# microcontroller.net
KiCad netlist of a schematic drawn in Altium Designer
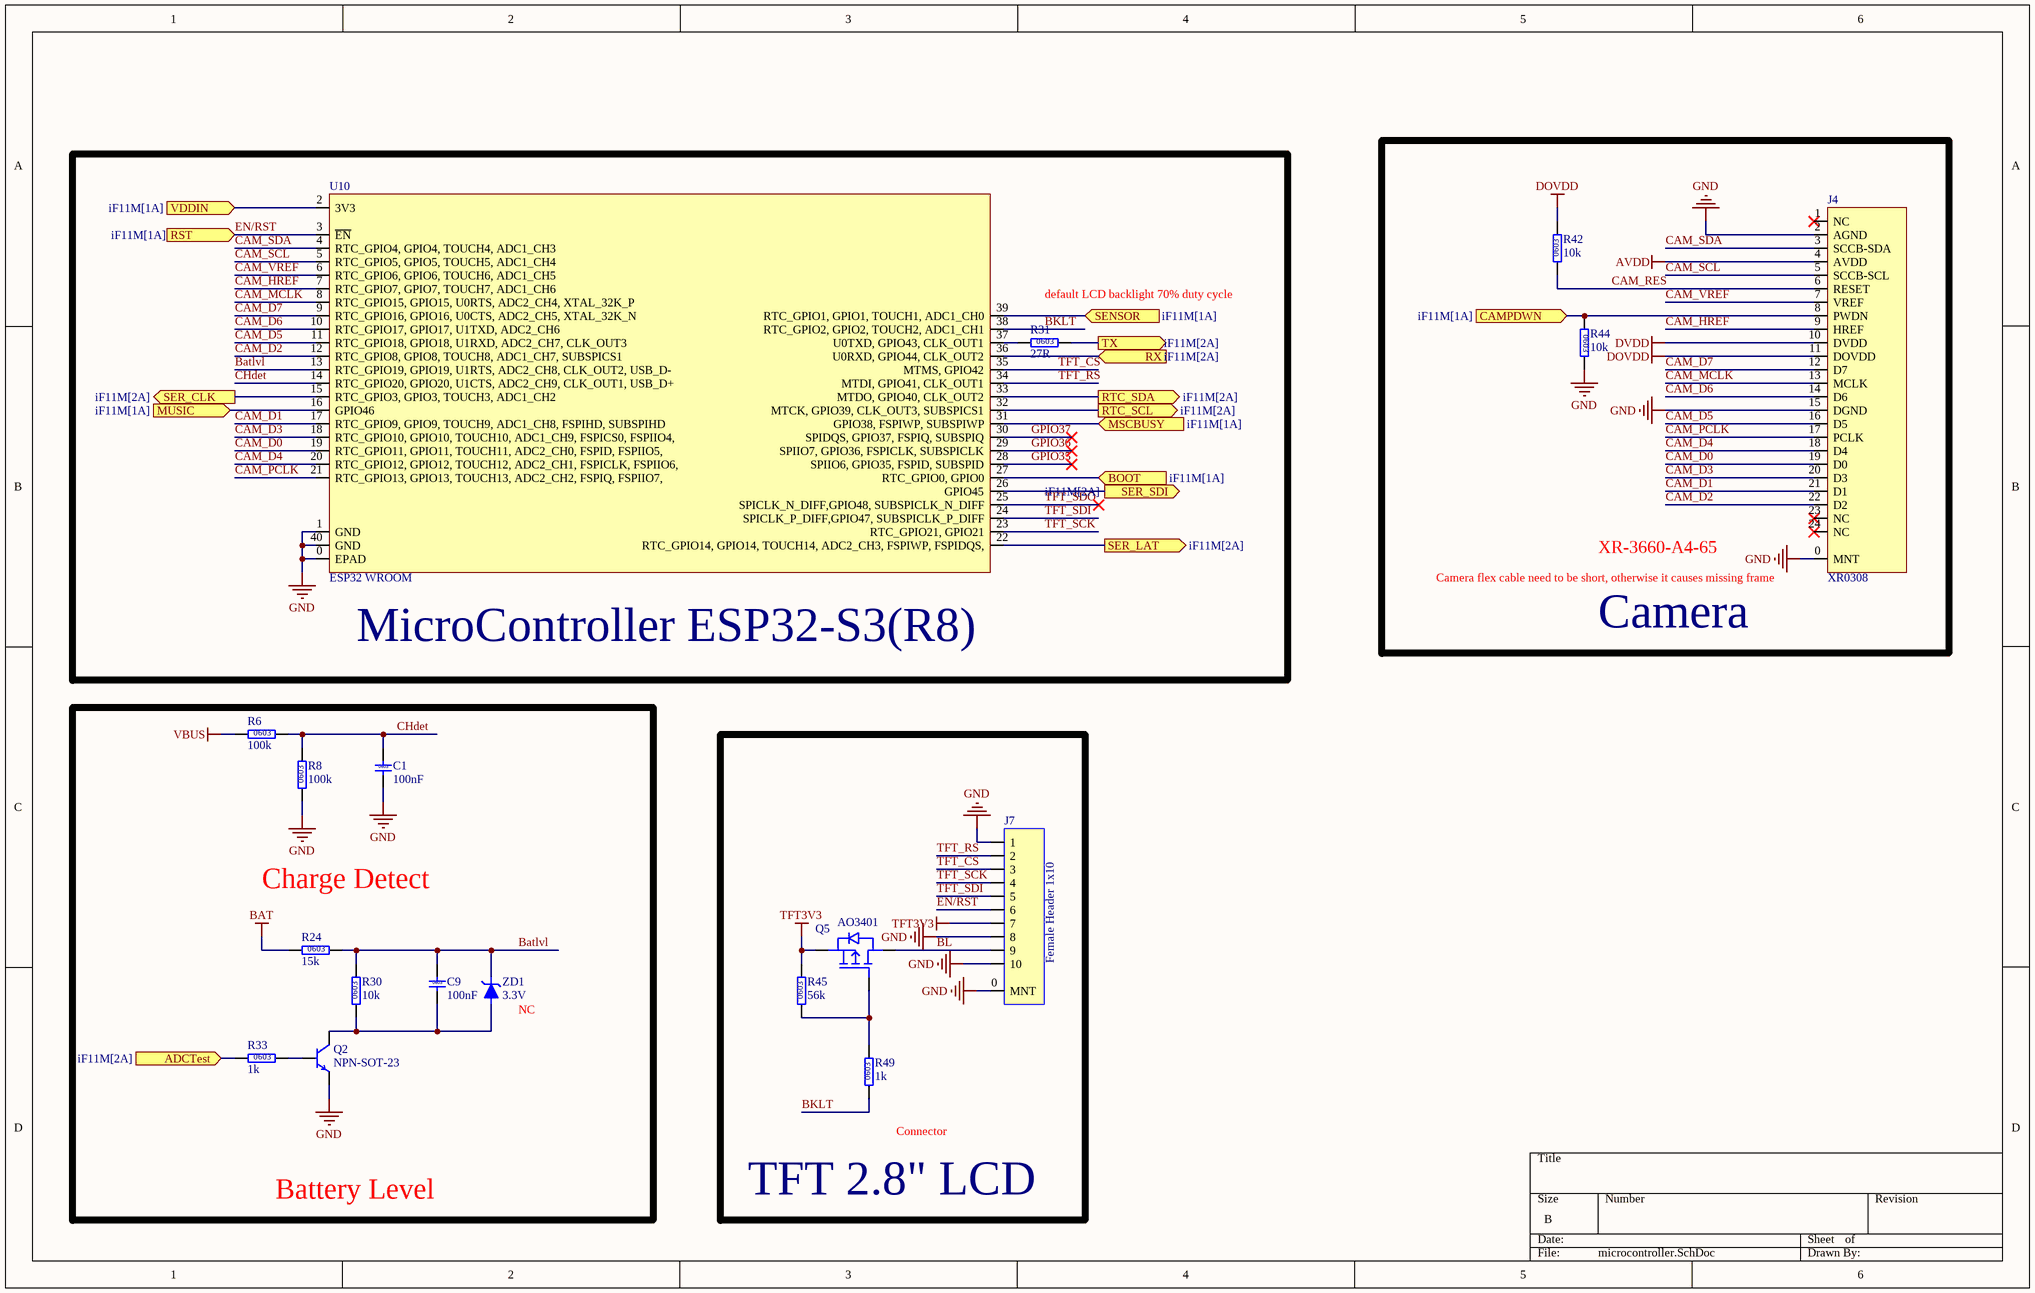
[diagram p0: microcontroller.SchDoc]

(export (version "E")
  (design (tool "Eeschema 10.0.6"))
  (components
    (comp (ref "C1")
      (value "100nF")
      (footprint "C0603")
      (description "10% 50V")
      (fields (field (name "PART NO") "W-T-CA-X703N100K50VNT") (field (name "MANUFACTURER") "FENGHUA"))
      (libsource (lib "Rescap") (part "C 0603 100nF 50V"))
    )
    (comp (ref "C9")
      (value "100nF")
      (footprint "C0603")
      (description "10% 50V")
      (fields (field (name "PART NO") "W-T-CA-X703N100K50VNT") (field (name "MANUFACTURER") "FENGHUA"))
      (libsource (lib "Rescap") (part "C 0603 100nF 50V"))
    )
    (comp (ref "J4")
      (value "XR0308")
      (footprint "FPC24-0.5P-TOP")
      (libsource (lib "Connector") (part "XR0308-TOP"))
    )
    (comp (ref "J7")
      (value "Female Header 1x10")
      (footprint "FPC10-1mm-SMT  BOTTOM")
      (description "10 Pin FPC BOTTOM Contact")
      (libsource (lib "Connector") (part "FPC10P-1mm-BOT"))
    )
    (comp (ref "Q2")
      (value "NPN-SOT-23")
      (footprint "SOT23")
      (libsource (lib "Transistor") (part "NPN-SOT-23"))
    )
    (comp (ref "Q5")
      (value "AO3401")
      (footprint "PMOS-SOT23")
      (description "MOSFET-P-Channel")
      (libsource (lib "Transistor") (part "MOSFET-P-Channel"))
    )
    (comp (ref "R6")
      (value "100k")
      (footprint "R0603-LD")
      (description "5%")
      (fields (field (name "PART NO") "W-T-RE-RS03K104JT") (field (name "MANUFACTURER") "LAGEO"))
      (libsource (lib "Rescap") (part "R 0603 100k"))
    )
    (comp (ref "R8")
      (value "100k")
      (footprint "R0603-LD")
      (description "5%")
      (fields (field (name "PART NO") "W-T-RE-RS03K104JT") (field (name "MANUFACTURER") "LAGEO"))
      (libsource (lib "Rescap") (part "R 0603 100k"))
    )
    (comp (ref "R24")
      (value "15k")
      (footprint "R0603-LD")
      (description "5%")
      (fields (field (name "PART NO") "W-T-RE-RS03K104JT") (field (name "MANUFACTURER") "LAGEO"))
      (libsource (lib "Rescap") (part "R 0603 100k"))
    )
    (comp (ref "R30")
      (value "10k")
      (footprint "R0603-LD")
      (description "5%")
      (fields (field (name "PART NO") "W-T-RE-RS03K104JT") (field (name "MANUFACTURER") "LAGEO"))
      (libsource (lib "Rescap") (part "R 0603 100k"))
    )
    (comp (ref "R31")
      (value "27R")
      (footprint "R0603-LD")
      (description "5%")
      (fields (field (name "PART NO") "W-T-RE-RS03K270JT") (field (name "MANUFACTURER") "LAGEO"))
      (libsource (lib "Rescap") (part "R 0603 27R"))
    )
    (comp (ref "R33")
      (value "1k")
      (footprint "R0603-LD")
      (description "5%")
      (fields (field (name "PART NO") "W-T-RE-RS03K102JT") (field (name "MANUFACTURER") "LAGEO"))
      (libsource (lib "Rescap") (part "R 0603 1k"))
    )
    (comp (ref "R42")
      (value "10k")
      (footprint "R0603-LD")
      (description "5%")
      (fields (field (name "PART NO") "W-T-RE-RS03K103JT") (field (name "MANUFACTURER") "热敏D541V11增加1颗用量"))
      (libsource (lib "Rescap") (part "R 0603 10k"))
    )
    (comp (ref "R44")
      (value "10k")
      (footprint "R0603-LD")
      (description "5%")
      (fields (field (name "PART NO") "W-T-RE-RS03K103JT") (field (name "MANUFACTURER") "热敏D541V11增加1颗用量"))
      (libsource (lib "Rescap") (part "R 0603 10k"))
    )
    (comp (ref "R45")
      (value "56k")
      (footprint "R0603-LD")
      (description "5%")
      (fields (field (name "PART NO") "W-T-RE-RS03K563JT") (field (name "MANUFACTURER") "LAGEO"))
      (libsource (lib "Rescap") (part "R 0603 56k"))
    )
    (comp (ref "R49")
      (value "1k")
      (footprint "R0603-LD")
      (description "5%")
      (fields (field (name "PART NO") "W-T-RE-RS03K102JT") (field (name "MANUFACTURER") "LAGEO"))
      (libsource (lib "Rescap") (part "R 0603 1k"))
    )
    (comp (ref "U10")
      (value "ESP32 WROOM")
      (footprint "ESP32-S3-WROOM-1")
      (libsource (lib "ICs") (part "ESP32-S3-WROOM-1"))
    )
    (comp (ref "ZD1")
      (value "3.3V")
      (footprint "SOD-323")
      (description "Zener Diode 300mW")
      (libsource (lib "Rectifier") (part "Zener Diode"))
    )
  )
  (nets
    (net (code "1") (name "/ADCTest") (class "Default")
      (node (ref "R33") (pin "1") (pinfunction "1_1") (pintype "passive"))
    )
    (net (code "2") (name "/BKLT") (class "Default")
      (node (ref "R49") (pin "1") (pinfunction "1_1") (pintype "passive"))
      (node (ref "U10") (pin "38") (pinfunction "RTC_GPIO2,_GPIO2,_TOUCH2,_ADC1_CH1_38") (pintype "passive"))
    )
    (net (code "3") (name "/BL") (class "Default")
      (node (ref "J7") (pin "9") (pinfunction "9_9") (pintype "passive"))
      (node (ref "Q5") (pin "2") (pinfunction "D_2") (pintype "passive"))
    )
    (net (code "4") (name "/BOOT") (class "Default")
      (node (ref "U10") (pin "27") (pinfunction "RTC_GPIO0,_GPIO0_27") (pintype "passive"))
    )
    (net (code "5") (name "/Batlvl") (class "Default")
      (node (ref "C9") (pin "1") (pinfunction "1_1") (pintype "passive"))
      (node (ref "R24") (pin "2") (pinfunction "2_2") (pintype "passive"))
      (node (ref "R30") (pin "2") (pinfunction "2_2") (pintype "passive"))
      (node (ref "U10") (pin "13") (pinfunction "RTC_GPIO19,_GPIO19,_U1RTS,_ADC2_CH8,_CLK_OUT2,_USB_D-_13") (pintype "passive"))
      (node (ref "ZD1") (pin "2") (pinfunction "K_2") (pintype "passive"))
    )
    (net (code "6") (name "/CAMPDWN") (class "Default")
      (node (ref "J4") (pin "8") (pinfunction "PWDN_8") (pintype "passive"))
      (node (ref "R44") (pin "1") (pinfunction "1_1") (pintype "passive"))
    )
    (net (code "7") (name "/CAM_D0") (class "Default")
      (node (ref "J4") (pin "19") (pinfunction "D0_19") (pintype "passive"))
      (node (ref "U10") (pin "19") (pinfunction "RTC_GPIO11,_GPIO11,_TOUCH11,_ADC2_CH0,_FSPID,_FSPIIO5,_19") (pintype "passive"))
    )
    (net (code "8") (name "/CAM_D1") (class "Default")
      (node (ref "J4") (pin "21") (pinfunction "D1_21") (pintype "passive"))
      (node (ref "U10") (pin "17") (pinfunction "RTC_GPIO9,_GPIO9,_TOUCH9,_ADC1_CH8,_FSPIHD,_SUBSPIHD_17") (pintype "passive"))
    )
    (net (code "9") (name "/CAM_D2") (class "Default")
      (node (ref "J4") (pin "22") (pinfunction "D2_22") (pintype "passive"))
      (node (ref "U10") (pin "12") (pinfunction "RTC_GPIO8,_GPIO8,_TOUCH8,_ADC1_CH7,_SUBSPICS1_12") (pintype "passive"))
    )
    (net (code "10") (name "/CAM_D3") (class "Default")
      (node (ref "J4") (pin "20") (pinfunction "D3_20") (pintype "passive"))
      (node (ref "U10") (pin "18") (pinfunction "RTC_GPIO10,_GPIO10,_TOUCH10,_ADC1_CH9,_FSPICS0,_FSPIIO4,_18") (pintype "passive"))
    )
    (net (code "11") (name "/CAM_D4") (class "Default")
      (node (ref "J4") (pin "18") (pinfunction "D4_18") (pintype "passive"))
      (node (ref "U10") (pin "20") (pinfunction "RTC_GPIO12,_GPIO12,_TOUCH12,_ADC2_CH1,_FSPICLK,_FSPIIO6,_20") (pintype "passive"))
    )
    (net (code "12") (name "/CAM_D5") (class "Default")
      (node (ref "J4") (pin "16") (pinfunction "D5_16") (pintype "passive"))
      (node (ref "U10") (pin "11") (pinfunction "RTC_GPIO18,_GPIO18,_U1RXD,_ADC2_CH7,_CLK_OUT3_11") (pintype "passive"))
    )
    (net (code "13") (name "/CAM_D6") (class "Default")
      (node (ref "J4") (pin "14") (pinfunction "D6_14") (pintype "passive"))
      (node (ref "U10") (pin "10") (pinfunction "RTC_GPIO17,_GPIO17,_U1TXD,_ADC2_CH6_10") (pintype "passive"))
    )
    (net (code "14") (name "/CAM_D7") (class "Default")
      (node (ref "J4") (pin "12") (pinfunction "D7_12") (pintype "passive"))
      (node (ref "U10") (pin "9") (pinfunction "RTC_GPIO16,_GPIO16,_U0CTS,_ADC2_CH5,_XTAL_32K_N_9") (pintype "passive"))
    )
    (net (code "15") (name "/CAM_HREF") (class "Default")
      (node (ref "J4") (pin "9") (pinfunction "HREF_9") (pintype "passive"))
      (node (ref "U10") (pin "7") (pinfunction "RTC_GPIO7,_GPIO7,_TOUCH7,_ADC1_CH6_7") (pintype "passive"))
    )
    (net (code "16") (name "/CAM_MCLK") (class "Default")
      (node (ref "J4") (pin "13") (pinfunction "MCLK_13") (pintype "passive"))
      (node (ref "U10") (pin "8") (pinfunction "RTC_GPIO15,_GPIO15,_U0RTS,_ADC2_CH4,_XTAL_32K_P_8") (pintype "passive"))
    )
    (net (code "17") (name "/CAM_PCLK") (class "Default")
      (node (ref "J4") (pin "17") (pinfunction "PCLK_17") (pintype "passive"))
      (node (ref "U10") (pin "21") (pinfunction "RTC_GPIO13,_GPIO13,_TOUCH13,_ADC2_CH2,_FSPIQ,_FSPIIO7,_21") (pintype "passive"))
    )
    (net (code "18") (name "/CAM_RES") (class "Default")
      (node (ref "J4") (pin "6") (pinfunction "RESET_6") (pintype "passive"))
      (node (ref "R42") (pin "1") (pinfunction "1_1") (pintype "passive"))
    )
    (net (code "19") (name "/CAM_SCL") (class "Default")
      (node (ref "J4") (pin "5") (pinfunction "SCCB-SCL_5") (pintype "passive"))
      (node (ref "U10") (pin "5") (pinfunction "RTC_GPIO5,_GPIO5,_TOUCH5,_ADC1_CH4_5") (pintype "passive"))
    )
    (net (code "20") (name "/CAM_SDA") (class "Default")
      (node (ref "J4") (pin "3") (pinfunction "SCCB-SDA_3") (pintype "passive"))
      (node (ref "U10") (pin "4") (pinfunction "RTC_GPIO4,_GPIO4,_TOUCH4,_ADC1_CH3_4") (pintype "passive"))
    )
    (net (code "21") (name "/CAM_VREF") (class "Default")
      (node (ref "J4") (pin "7") (pinfunction "VREF_7") (pintype "passive"))
      (node (ref "U10") (pin "6") (pinfunction "RTC_GPIO6,_GPIO6,_TOUCH6,_ADC1_CH5_6") (pintype "passive"))
    )
    (net (code "22") (name "/CHdet") (class "Default")
      (node (ref "C1") (pin "1") (pinfunction "1_1") (pintype "passive"))
      (node (ref "R6") (pin "2") (pinfunction "2_2") (pintype "passive"))
      (node (ref "R8") (pin "2") (pinfunction "2_2") (pintype "passive"))
      (node (ref "U10") (pin "14") (pinfunction "RTC_GPIO20,_GPIO20,_U1CTS,_ADC2_CH9,_CLK_OUT1,_USB_D+_14") (pintype "passive"))
    )
    (net (code "23") (name "/EN{slash}RST") (class "Default")
      (node (ref "J7") (pin "6") (pinfunction "6_6") (pintype "passive"))
      (node (ref "U10") (pin "3") (pinfunction "~{EN}_3") (pintype "passive"))
    )
    (net (code "24") (name "/GPIO35") (class "Default")
      (node (ref "U10") (pin "28") (pinfunction "SPIIO6,_GPIO35,_FSPID,_SUBSPID_28") (pintype "passive+no_connect"))
    )
    (net (code "25") (name "/GPIO36") (class "Default")
      (node (ref "U10") (pin "29") (pinfunction "SPIIO7,_GPIO36,_FSPICLK,_SUBSPICLK_29") (pintype "passive+no_connect"))
    )
    (net (code "26") (name "/GPIO37") (class "Default")
      (node (ref "U10") (pin "30") (pinfunction "SPIDQS,_GPIO37,_FSPIQ,_SUBSPIQ_30") (pintype "passive+no_connect"))
    )
    (net (code "27") (name "/MSCBUSY") (class "Default")
      (node (ref "U10") (pin "31") (pinfunction "GPIO38,_FSPIWP,_SUBSPIWP_31") (pintype "passive"))
    )
    (net (code "28") (name "/MUSIC") (class "Default")
      (node (ref "U10") (pin "16") (pinfunction "GPIO46_16") (pintype "passive"))
    )
    (net (code "29") (name "/RTC_SCL") (class "Default")
      (node (ref "U10") (pin "32") (pinfunction "MTCK,_GPIO39,_CLK_OUT3,_SUBSPICS1_32") (pintype "passive"))
    )
    (net (code "30") (name "/RTC_SDA") (class "Default")
      (node (ref "U10") (pin "33") (pinfunction "MTDO,_GPIO40,_CLK_OUT2_33") (pintype "passive"))
    )
    (net (code "31") (name "/RX") (class "Default")
      (node (ref "U10") (pin "36") (pinfunction "U0RXD,_GPIO44,_CLK_OUT2_36") (pintype "passive"))
    )
    (net (code "32") (name "/SENSOR") (class "Default")
      (node (ref "U10") (pin "39") (pinfunction "RTC_GPIO1,_GPIO1,_TOUCH1,_ADC1_CH0_39") (pintype "passive"))
    )
    (net (code "33") (name "/SER_CLK") (class "Default")
      (node (ref "U10") (pin "15") (pinfunction "RTC_GPIO3,_GPIO3,_TOUCH3,_ADC1_CH2_15") (pintype "passive"))
    )
    (net (code "34") (name "/SER_LAT") (class "Default")
      (node (ref "U10") (pin "22") (pinfunction "RTC_GPIO14,_GPIO14,_TOUCH14,_ADC2_CH3,_FSPIWP,_FSPIDQS,_22") (pintype "passive"))
    )
    (net (code "35") (name "/SER_SDI") (class "Default")
      (node (ref "U10") (pin "26") (pinfunction "GPIO45_26") (pintype "passive"))
    )
    (net (code "36") (name "/TFT_CS") (class "Default")
      (node (ref "J7") (pin "3") (pinfunction "3_3") (pintype "passive"))
      (node (ref "U10") (pin "35") (pinfunction "MTMS,_GPIO42_35") (pintype "passive"))
    )
    (net (code "37") (name "/TFT_RS") (class "Default")
      (node (ref "J7") (pin "2") (pinfunction "2_2") (pintype "passive"))
      (node (ref "U10") (pin "34") (pinfunction "MTDI,_GPIO41,_CLK_OUT1_34") (pintype "passive"))
    )
    (net (code "38") (name "/TFT_SCK") (class "Default")
      (node (ref "J7") (pin "4") (pinfunction "4_4") (pintype "passive"))
      (node (ref "U10") (pin "23") (pinfunction "RTC_GPIO21,_GPIO21_23") (pintype "passive"))
    )
    (net (code "39") (name "/TFT_SDI") (class "Default")
      (node (ref "J7") (pin "5") (pinfunction "5_5") (pintype "passive"))
      (node (ref "U10") (pin "24") (pinfunction "SPICLK_P_DIFF,GPIO47,_SUBSPICLK_P_DIFF_24") (pintype "passive"))
    )
    (net (code "40") (name "/TFT_SDO") (class "Default")
      (node (ref "U10") (pin "25") (pinfunction "SPICLK_N_DIFF,GPIO48,_SUBSPICLK_N_DIFF_25") (pintype "passive+no_connect"))
    )
    (net (code "41") (name "/TX") (class "Default")
      (node (ref "R31") (pin "2") (pinfunction "2_2") (pintype "passive"))
    )
    (net (code "42") (name "/VDDIN") (class "Default")
      (node (ref "U10") (pin "2") (pinfunction "3V3_2") (pintype "passive"))
    )
    (net (code "43") (name "AVDD") (class "Default")
      (node (ref "J4") (pin "4") (pinfunction "AVDD_4") (pintype "passive"))
    )
    (net (code "44") (name "BAT") (class "Default")
      (node (ref "R24") (pin "1") (pinfunction "1_1") (pintype "passive"))
    )
    (net (code "45") (name "DOVDD") (class "Default")
      (node (ref "J4") (pin "11") (pinfunction "DOVDD_11") (pintype "passive"))
      (node (ref "R42") (pin "2") (pinfunction "2_2") (pintype "passive"))
    )
    (net (code "46") (name "DVDD") (class "Default")
      (node (ref "J4") (pin "10") (pinfunction "DVDD_10") (pintype "passive"))
    )
    (net (code "47") (name "GND") (class "Default")
      (node (ref "C1") (pin "2") (pinfunction "2_2") (pintype "passive"))
      (node (ref "J4") (pin "0") (pinfunction "MNT_0") (pintype "passive"))
      (node (ref "J4") (pin "15") (pinfunction "DGND_15") (pintype "passive"))
      (node (ref "J4") (pin "2") (pinfunction "AGND_2") (pintype "passive"))
      (node (ref "J7") (pin "0") (pinfunction "MNT_0") (pintype "passive"))
      (node (ref "J7") (pin "1") (pinfunction "1_1") (pintype "passive"))
      (node (ref "J7") (pin "10") (pinfunction "10_10") (pintype "passive"))
      (node (ref "J7") (pin "8") (pinfunction "8_8") (pintype "passive"))
      (node (ref "Q2") (pin "2") (pinfunction "E_2") (pintype "passive"))
      (node (ref "R44") (pin "2") (pinfunction "2_2") (pintype "passive"))
      (node (ref "R8") (pin "1") (pinfunction "1_1") (pintype "passive"))
      (node (ref "U10") (pin "0") (pinfunction "EPAD_0") (pintype "passive"))
      (node (ref "U10") (pin "1") (pinfunction "GND_1") (pintype "passive"))
      (node (ref "U10") (pin "40") (pinfunction "GND_40") (pintype "passive"))
    )
    (net (code "48") (name "Net-(Q2-B)") (class "Default")
      (node (ref "Q2") (pin "1") (pinfunction "B_1") (pintype "passive"))
      (node (ref "R33") (pin "2") (pinfunction "2_2") (pintype "passive"))
    )
    (net (code "49") (name "Net-(Q2-C)") (class "Default")
      (node (ref "C9") (pin "2") (pinfunction "2_2") (pintype "passive"))
      (node (ref "Q2") (pin "3") (pinfunction "C_3") (pintype "passive"))
      (node (ref "R30") (pin "1") (pinfunction "1_1") (pintype "passive"))
      (node (ref "ZD1") (pin "1") (pinfunction "A_1") (pintype "passive"))
    )
    (net (code "50") (name "Net-(Q5-G)") (class "Default")
      (node (ref "Q5") (pin "1") (pinfunction "G_1") (pintype "passive"))
      (node (ref "R45") (pin "1") (pinfunction "1_1") (pintype "passive"))
      (node (ref "R49") (pin "2") (pinfunction "2_2") (pintype "passive"))
    )
    (net (code "51") (name "Net-(U10-U0TXD,_GPIO43,_CLK_OUT1)") (class "Default")
      (node (ref "R31") (pin "1") (pinfunction "1_1") (pintype "passive"))
      (node (ref "U10") (pin "37") (pinfunction "U0TXD,_GPIO43,_CLK_OUT1_37") (pintype "passive"))
    )
    (net (code "52") (name "TFT3V3") (class "Default")
      (node (ref "J7") (pin "7") (pinfunction "7_7") (pintype "passive"))
      (node (ref "Q5") (pin "3") (pinfunction "S_3") (pintype "passive"))
      (node (ref "R45") (pin "2") (pinfunction "2_2") (pintype "passive"))
    )
    (net (code "53") (name "VBUS") (class "Default")
      (node (ref "R6") (pin "1") (pinfunction "1_1") (pintype "passive"))
    )
    (net (code "54") (name "unconnected-(J4-NC-Pad1)") (class "Default")
      (node (ref "J4") (pin "1") (pinfunction "NC_1") (pintype "passive+no_connect"))
    )
    (net (code "55") (name "unconnected-(J4-NC-Pad23)") (class "Default")
      (node (ref "J4") (pin "23") (pinfunction "NC_23") (pintype "passive+no_connect"))
    )
    (net (code "56") (name "unconnected-(J4-NC-Pad24)") (class "Default")
      (node (ref "J4") (pin "24") (pinfunction "NC_24") (pintype "passive+no_connect"))
    )
  )
)
